# Solar_Panel_Support.net
KiCad netlist of a schematic drawn in EAGLE
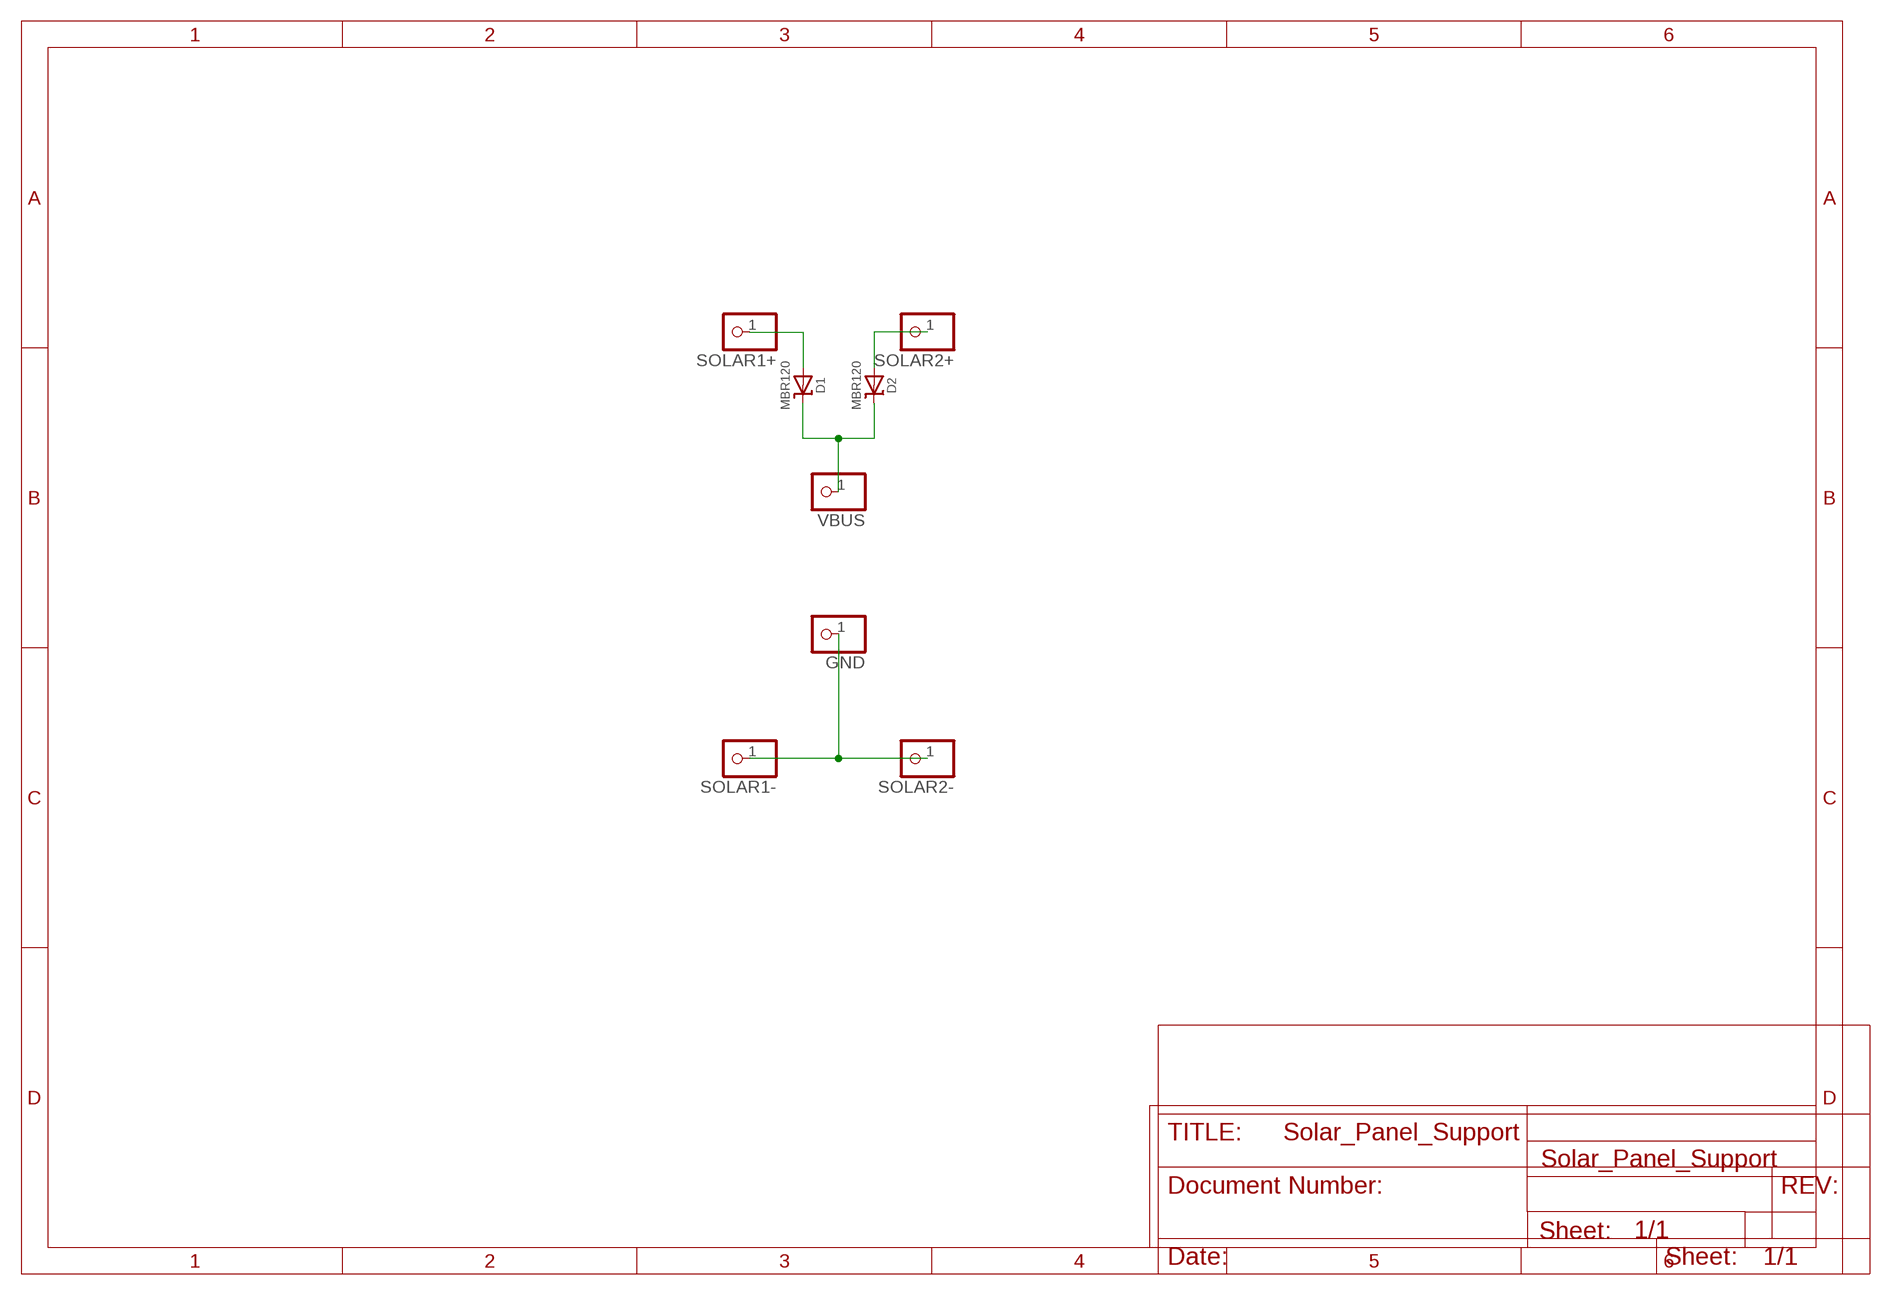
[diagram p0: schematic, sheet 1]

(export (version "E")
  (design (tool "Eeschema 10.0.6"))
  (components
    (comp (ref "D1")
      (value "MBR120")
      (footprint "eagle-import:SOD-123")
      (libsource (lib "eagle-import") (part "DIODE-SCHOTTKYSOD-123"))
    )
    (comp (ref "D2")
      (value "MBR120")
      (footprint "eagle-import:SOD-123")
      (libsource (lib "eagle-import") (part "DIODE-SCHOTTKYSOD-123"))
    )
    (comp (ref "GND")
      (value "PINHD-1X1")
      (footprint "eagle-import:1X01")
      (libsource (lib "eagle-import") (part "PINHD-1X1"))
    )
    (comp (ref "SOLAR1+")
      (value "PINHD-1X1")
      (footprint "eagle-import:1X01")
      (libsource (lib "eagle-import") (part "PINHD-1X1"))
    )
    (comp (ref "SOLAR1-")
      (value "PINHD-1X1")
      (footprint "eagle-import:1X01")
      (libsource (lib "eagle-import") (part "PINHD-1X1"))
    )
    (comp (ref "SOLAR2+")
      (value "PINHD-1X1")
      (footprint "eagle-import:1X01")
      (libsource (lib "eagle-import") (part "PINHD-1X1"))
    )
    (comp (ref "SOLAR2-")
      (value "PINHD-1X1")
      (footprint "eagle-import:1X01")
      (libsource (lib "eagle-import") (part "PINHD-1X1"))
    )
    (comp (ref "VBUS")
      (value "PINHD-1X1")
      (footprint "eagle-import:1X01")
      (libsource (lib "eagle-import") (part "PINHD-1X1"))
    )
  )
  (nets
    (net (code "1") (name "Net-(D1-PadA)") (class "Default")
      (node (ref "D1") (pin "A") (pinfunction "A_A") (pintype "passive"))
      (node (ref "SOLAR1+") (pin "1") (pinfunction "1_1") (pintype "passive"))
    )
    (net (code "2") (name "Net-(D1-PadC)") (class "Default")
      (node (ref "D1") (pin "C") (pinfunction "C_C") (pintype "passive"))
      (node (ref "D2") (pin "C") (pinfunction "C_C") (pintype "passive"))
      (node (ref "VBUS") (pin "1") (pinfunction "1_1") (pintype "passive"))
    )
    (net (code "3") (name "Net-(D2-PadA)") (class "Default")
      (node (ref "D2") (pin "A") (pinfunction "A_A") (pintype "passive"))
      (node (ref "SOLAR2+") (pin "1") (pinfunction "1_1") (pintype "passive"))
    )
    (net (code "4") (name "Net-(GND-Pad1)") (class "Default")
      (node (ref "GND") (pin "1") (pinfunction "1_1") (pintype "passive"))
      (node (ref "SOLAR1-") (pin "1") (pinfunction "1_1") (pintype "passive"))
      (node (ref "SOLAR2-") (pin "1") (pinfunction "1_1") (pintype "passive"))
    )
  )
)
